# LiPo_Recharging_Circuit_Schematic_v_20.net
KiCad netlist of a schematic drawn in Altium Designer
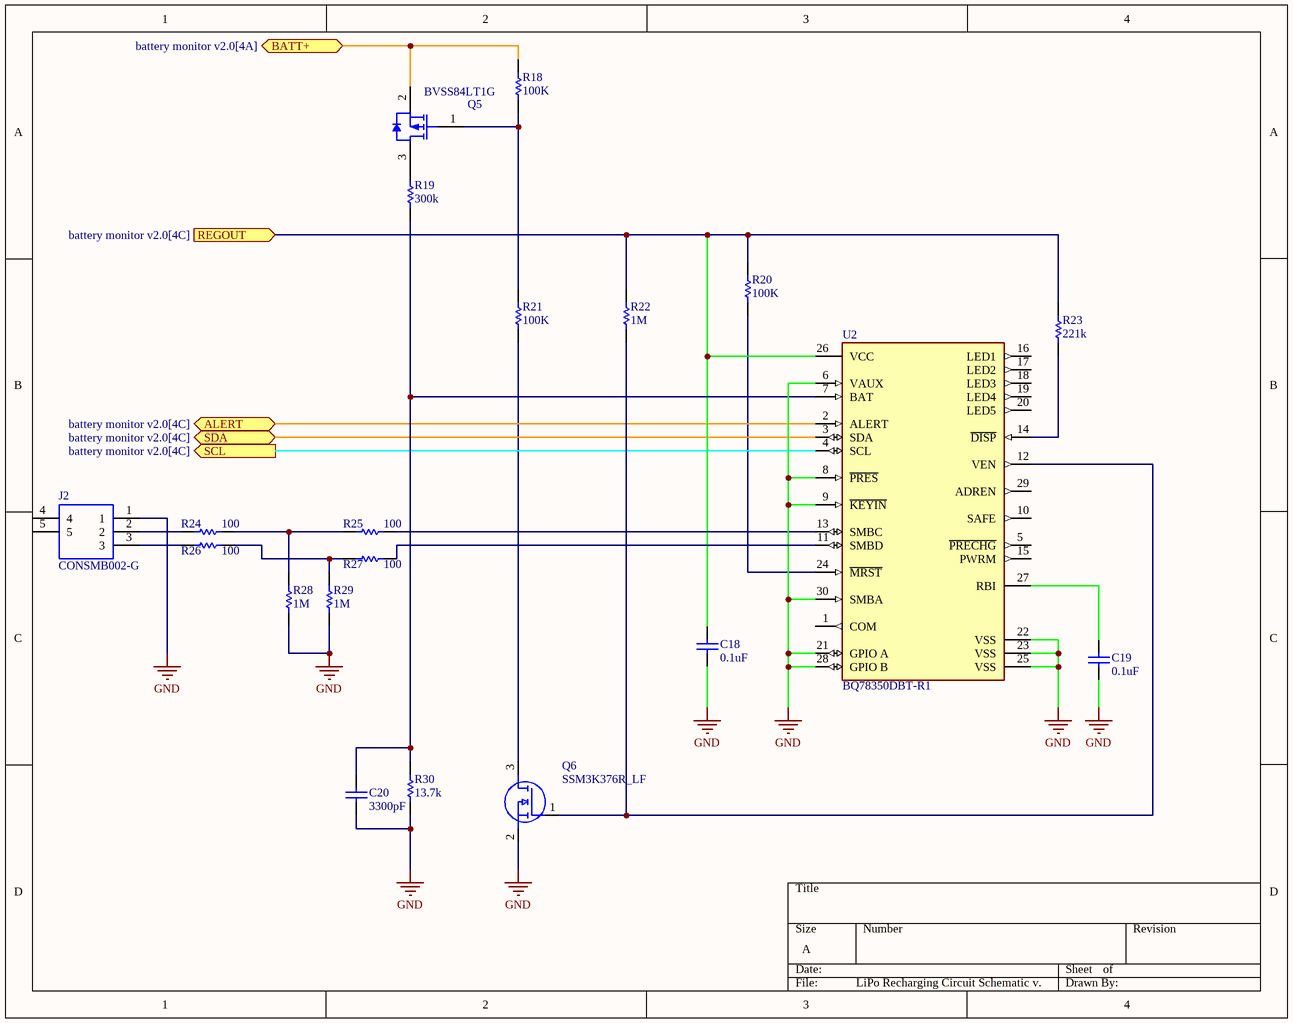
[diagram p0: LiPo Recharging Circuit Schematic v.20.SchDoc]

(export (version "E")
  (design (tool "Eeschema 10.0.6"))
  (components
    (comp (ref "C18")
      (value "0.1uF")
      (footprint "CAPC2012X145N:CAPC2012X145N")
      (description "Capacitor")
      (libsource (lib "Simulation Generic Components") (part "Capacitor"))
    )
    (comp (ref "C19")
      (value "0.1uF")
      (footprint "CAPC2012X145N:CAPC2012X145N")
      (description "Capacitor")
      (libsource (lib "Simulation Generic Components") (part "Capacitor"))
    )
    (comp (ref "C20")
      (value "3300pF")
      (footprint "CAPC2012X145N:CAPC2012X145N")
      (description "Capacitor")
      (libsource (lib "Simulation Generic Components") (part "Capacitor"))
    )
    (comp (ref "J2")
      (value "CONSMB002-G")
      (footprint "CONSMB002G:CONSMB002G")
      (fields (field (name "MOUSER PART NUMBER") "712-CONSMB002-G"))
      (libsource (lib "CONSMB002-G") (part "CONSMB002-G"))
    )
    (comp (ref "Q5")
      (value "BVSS84LT1G")
      (footprint "ONSC-SOT-23-3-318-08_V")
      (description "Power MOSFET Single P-Channel, -50 V, 10 Ohm, 3-Pin SOT-23, Pb-Free, Tape and Reel")
      (fields (field (name "MANUFACTURER") "On Semiconductor"))
      (libsource (lib "Altium Content Vault") (part "ONSC-PMOS-G1S2D3-3_D"))
    )
    (comp (ref "Q6")
      (value "SSM3K376R_LF")
      (footprint "SSM3K376RLF:SSM3K376RLF")
      (description "Trans MOSFET N-CH Si 30V 4A Automotive 3-Pin SOT-23F T/R")
      (fields
        (field (name "MOUSER PART NUMBER") "757-SSM3K376RLF")
        (field (name "MANUFACTURER_PART_NUMBER") "SSM3K376R,LF")
      )
      (libsource (lib "SSM3K376R_LF") (part "SSM3K376R_LF"))
    )
    (comp (ref "R18")
      (value "100K")
      (footprint "CAPC2012X145N:CAPC2012X145N")
      (description "Resistor")
      (libsource (lib "Simulation Generic Components") (part "Resistor"))
    )
    (comp (ref "R19")
      (value "300k")
      (footprint "CAPC2012X145N:CAPC2012X145N")
      (description "Resistor")
      (libsource (lib "Simulation Generic Components") (part "Resistor"))
    )
    (comp (ref "R20")
      (value "100K")
      (footprint "CAPC2012X145N:CAPC2012X145N")
      (description "Resistor")
      (libsource (lib "Simulation Generic Components") (part "Resistor"))
    )
    (comp (ref "R21")
      (value "100K")
      (footprint "CAPC2012X145N:CAPC2012X145N")
      (description "Resistor")
      (libsource (lib "Simulation Generic Components") (part "Resistor"))
    )
    (comp (ref "R22")
      (value "1M")
      (footprint "CAPC2012X145N:CAPC2012X145N")
      (description "Resistor")
      (libsource (lib "Simulation Generic Components") (part "Resistor"))
    )
    (comp (ref "R23")
      (value "221k")
      (footprint "CAPC2012X145N:CAPC2012X145N")
      (description "Resistor")
      (libsource (lib "Simulation Generic Components") (part "Resistor"))
    )
    (comp (ref "R24")
      (value "100")
      (footprint "CAPC2012X145N:CAPC2012X145N")
      (description "Resistor")
      (libsource (lib "Simulation Generic Components") (part "Resistor"))
    )
    (comp (ref "R25")
      (value "100")
      (footprint "CAPC2012X145N:CAPC2012X145N")
      (description "Resistor")
      (libsource (lib "Simulation Generic Components") (part "Resistor"))
    )
    (comp (ref "R26")
      (value "100")
      (footprint "CAPC2012X145N:CAPC2012X145N")
      (description "Resistor")
      (libsource (lib "Simulation Generic Components") (part "Resistor"))
    )
    (comp (ref "R27")
      (value "100")
      (footprint "CAPC2012X145N:CAPC2012X145N")
      (description "Resistor")
      (libsource (lib "Simulation Generic Components") (part "Resistor"))
    )
    (comp (ref "R28")
      (value "1M")
      (footprint "CAPC2012X145N:CAPC2012X145N")
      (description "Resistor")
      (libsource (lib "Simulation Generic Components") (part "Resistor"))
    )
    (comp (ref "R29")
      (value "1M")
      (footprint "CAPC2012X145N:CAPC2012X145N")
      (description "Resistor")
      (libsource (lib "Simulation Generic Components") (part "Resistor"))
    )
    (comp (ref "R30")
      (value "13.7k")
      (footprint "CAPC2012X145N:CAPC2012X145N")
      (description "Resistor")
      (libsource (lib "Simulation Generic Components") (part "Resistor"))
    )
    (comp (ref "U2")
      (value "BQ78350DBT-R1")
      (footprint "FP-DBT0030A-IPC_C")
      (description "IC BATTERY MGMT CTRLR 30TSSOP")
      (libsource (lib "Altium Content Vault") (part "ce2f43281ae33b5194046e95201acc2"))
    )
  )
  (nets
    (net (code "1") (name "/ALERT") (class "Default")
      (node (ref "U2") (pin "2") (pinfunction "ALERT_2") (pintype "input"))
    )
    (net (code "2") (name "/BATT+") (class "Default")
      (node (ref "Q5") (pin "2") (pinfunction "S_2") (pintype "passive"))
      (node (ref "R18") (pin "2") (pinfunction "2_2") (pintype "passive"))
    )
    (net (code "3") (name "/REGOUT") (class "Default")
      (node (ref "C18") (pin "2") (pinfunction "2_2") (pintype "passive"))
      (node (ref "R20") (pin "2") (pinfunction "2_2") (pintype "passive"))
      (node (ref "R22") (pin "2") (pinfunction "2_2") (pintype "passive"))
      (node (ref "R23") (pin "2") (pinfunction "2_2") (pintype "passive"))
      (node (ref "U2") (pin "26") (pinfunction "VCC_26") (pintype "power_in"))
    )
    (net (code "4") (name "/SCL") (class "Default")
      (node (ref "U2") (pin "4") (pinfunction "SCL_4") (pintype "bidirectional"))
    )
    (net (code "5") (name "/SDA") (class "Default")
      (node (ref "U2") (pin "3") (pinfunction "SDA_3") (pintype "bidirectional"))
    )
    (net (code "6") (name "GND") (class "Default")
      (node (ref "C18") (pin "1") (pinfunction "1_1") (pintype "passive"))
      (node (ref "C19") (pin "1") (pinfunction "1_1") (pintype "passive"))
      (node (ref "C20") (pin "1") (pinfunction "1_1") (pintype "passive"))
      (node (ref "J2") (pin "1") (pinfunction "1_1") (pintype "passive"))
      (node (ref "Q6") (pin "2") (pinfunction "S_2") (pintype "passive"))
      (node (ref "R28") (pin "2") (pinfunction "2_2") (pintype "passive"))
      (node (ref "R29") (pin "1") (pinfunction "1_1") (pintype "passive"))
      (node (ref "R30") (pin "1") (pinfunction "1_1") (pintype "passive"))
      (node (ref "U2") (pin "21") (pinfunction "GPIO_A_21") (pintype "bidirectional"))
      (node (ref "U2") (pin "22") (pinfunction "VSS_22") (pintype "power_in"))
      (node (ref "U2") (pin "23") (pinfunction "VSS_23") (pintype "power_in"))
      (node (ref "U2") (pin "25") (pinfunction "VSS_25") (pintype "power_in"))
      (node (ref "U2") (pin "28") (pinfunction "GPIO_B_28") (pintype "bidirectional"))
      (node (ref "U2") (pin "30") (pinfunction "SMBA_30") (pintype "input"))
      (node (ref "U2") (pin "6") (pinfunction "VAUX_6") (pintype "input"))
      (node (ref "U2") (pin "8") (pinfunction "~{PRES}_8") (pintype "input"))
      (node (ref "U2") (pin "9") (pinfunction "~{KEYIN}_9") (pintype "input"))
    )
    (net (code "7") (name "Net-(J2-Pad2)") (class "Default")
      (node (ref "J2") (pin "2") (pinfunction "2_2") (pintype "passive"))
      (node (ref "R24") (pin "2") (pinfunction "2_2") (pintype "passive"))
    )
    (net (code "8") (name "Net-(J2-Pad3)") (class "Default")
      (node (ref "J2") (pin "3") (pinfunction "3_3") (pintype "passive"))
      (node (ref "R26") (pin "2") (pinfunction "2_2") (pintype "passive"))
    )
    (net (code "9") (name "Net-(Q5-D)") (class "Default")
      (node (ref "Q5") (pin "3") (pinfunction "D_3") (pintype "passive"))
      (node (ref "R19") (pin "2") (pinfunction "2_2") (pintype "passive"))
    )
    (net (code "10") (name "Net-(Q5-G)") (class "Default")
      (node (ref "Q5") (pin "1") (pinfunction "G_1") (pintype "passive"))
      (node (ref "R18") (pin "1") (pinfunction "1_1") (pintype "passive"))
      (node (ref "R21") (pin "2") (pinfunction "2_2") (pintype "passive"))
    )
    (net (code "11") (name "Net-(Q6-D)") (class "Default")
      (node (ref "Q6") (pin "3") (pinfunction "D_3") (pintype "passive"))
      (node (ref "R21") (pin "1") (pinfunction "1_1") (pintype "passive"))
    )
    (net (code "12") (name "Net-(Q6-G)") (class "Default")
      (node (ref "Q6") (pin "1") (pinfunction "G_1") (pintype "passive"))
      (node (ref "R22") (pin "1") (pinfunction "1_1") (pintype "passive"))
      (node (ref "U2") (pin "12") (pinfunction "VEN_12") (pintype "output"))
    )
    (net (code "13") (name "Net-(R24-Pad1)") (class "Default")
      (node (ref "R24") (pin "1") (pinfunction "1_1") (pintype "passive"))
      (node (ref "R25") (pin "2") (pinfunction "2_2") (pintype "passive"))
      (node (ref "R28") (pin "1") (pinfunction "1_1") (pintype "passive"))
    )
    (net (code "14") (name "Net-(R26-Pad1)") (class "Default")
      (node (ref "R26") (pin "1") (pinfunction "1_1") (pintype "passive"))
      (node (ref "R27") (pin "2") (pinfunction "2_2") (pintype "passive"))
      (node (ref "R29") (pin "2") (pinfunction "2_2") (pintype "passive"))
    )
    (net (code "15") (name "Net-(U2-BAT)") (class "Default")
      (node (ref "C20") (pin "2") (pinfunction "2_2") (pintype "passive"))
      (node (ref "R19") (pin "1") (pinfunction "1_1") (pintype "passive"))
      (node (ref "R30") (pin "2") (pinfunction "2_2") (pintype "passive"))
      (node (ref "U2") (pin "7") (pinfunction "BAT_7") (pintype "input"))
    )
    (net (code "16") (name "Net-(U2-RBI)") (class "Default")
      (node (ref "C19") (pin "2") (pinfunction "2_2") (pintype "passive"))
      (node (ref "U2") (pin "27") (pinfunction "RBI_27") (pintype "power_in"))
    )
    (net (code "17") (name "Net-(U2-SMBC)") (class "Default")
      (node (ref "R25") (pin "1") (pinfunction "1_1") (pintype "passive"))
      (node (ref "U2") (pin "13") (pinfunction "SMBC_13") (pintype "bidirectional"))
    )
    (net (code "18") (name "Net-(U2-SMBD)") (class "Default")
      (node (ref "R27") (pin "1") (pinfunction "1_1") (pintype "passive"))
      (node (ref "U2") (pin "11") (pinfunction "SMBD_11") (pintype "bidirectional"))
    )
    (net (code "19") (name "Net-(U2-~{DISP})") (class "Default")
      (node (ref "R23") (pin "1") (pinfunction "1_1") (pintype "passive"))
      (node (ref "U2") (pin "14") (pinfunction "~{DISP}_14") (pintype "input"))
    )
    (net (code "20") (name "Net-(U2-~{MRST})") (class "Default")
      (node (ref "R20") (pin "1") (pinfunction "1_1") (pintype "passive"))
      (node (ref "U2") (pin "24") (pinfunction "~{MRST}_24") (pintype "input"))
    )
    (net (code "21") (name "unconnected-(J2-Pad4)") (class "Default")
      (node (ref "J2") (pin "4") (pinfunction "4_4") (pintype "passive"))
    )
    (net (code "22") (name "unconnected-(J2-Pad5)") (class "Default")
      (node (ref "J2") (pin "5") (pinfunction "5_5") (pintype "passive"))
    )
    (net (code "23") (name "unconnected-(U2-ADREN-Pad29)") (class "Default")
      (node (ref "U2") (pin "29") (pinfunction "ADREN_29") (pintype "output"))
    )
    (net (code "24") (name "unconnected-(U2-COM-Pad1)") (class "Default")
      (node (ref "U2") (pin "1") (pinfunction "COM_1") (pintype "output"))
    )
    (net (code "25") (name "unconnected-(U2-LED1-Pad16)") (class "Default")
      (node (ref "U2") (pin "16") (pinfunction "LED1_16") (pintype "output"))
    )
    (net (code "26") (name "unconnected-(U2-LED2-Pad17)") (class "Default")
      (node (ref "U2") (pin "17") (pinfunction "LED2_17") (pintype "output"))
    )
    (net (code "27") (name "unconnected-(U2-LED3-Pad18)") (class "Default")
      (node (ref "U2") (pin "18") (pinfunction "LED3_18") (pintype "output"))
    )
    (net (code "28") (name "unconnected-(U2-LED4-Pad19)") (class "Default")
      (node (ref "U2") (pin "19") (pinfunction "LED4_19") (pintype "output"))
    )
    (net (code "29") (name "unconnected-(U2-LED5-Pad20)") (class "Default")
      (node (ref "U2") (pin "20") (pinfunction "LED5_20") (pintype "output"))
    )
    (net (code "30") (name "unconnected-(U2-PWRM-Pad15)") (class "Default")
      (node (ref "U2") (pin "15") (pinfunction "PWRM_15") (pintype "output"))
    )
    (net (code "31") (name "unconnected-(U2-SAFE-Pad10)") (class "Default")
      (node (ref "U2") (pin "10") (pinfunction "SAFE_10") (pintype "output"))
    )
    (net (code "32") (name "unconnected-(U2-~{PRECHG}-Pad5)") (class "Default")
      (node (ref "U2") (pin "5") (pinfunction "~{PRECHG}_5") (pintype "output"))
    )
  )
)
